# Sheet1.net
KiCad netlist of a schematic drawn in Altium Designer
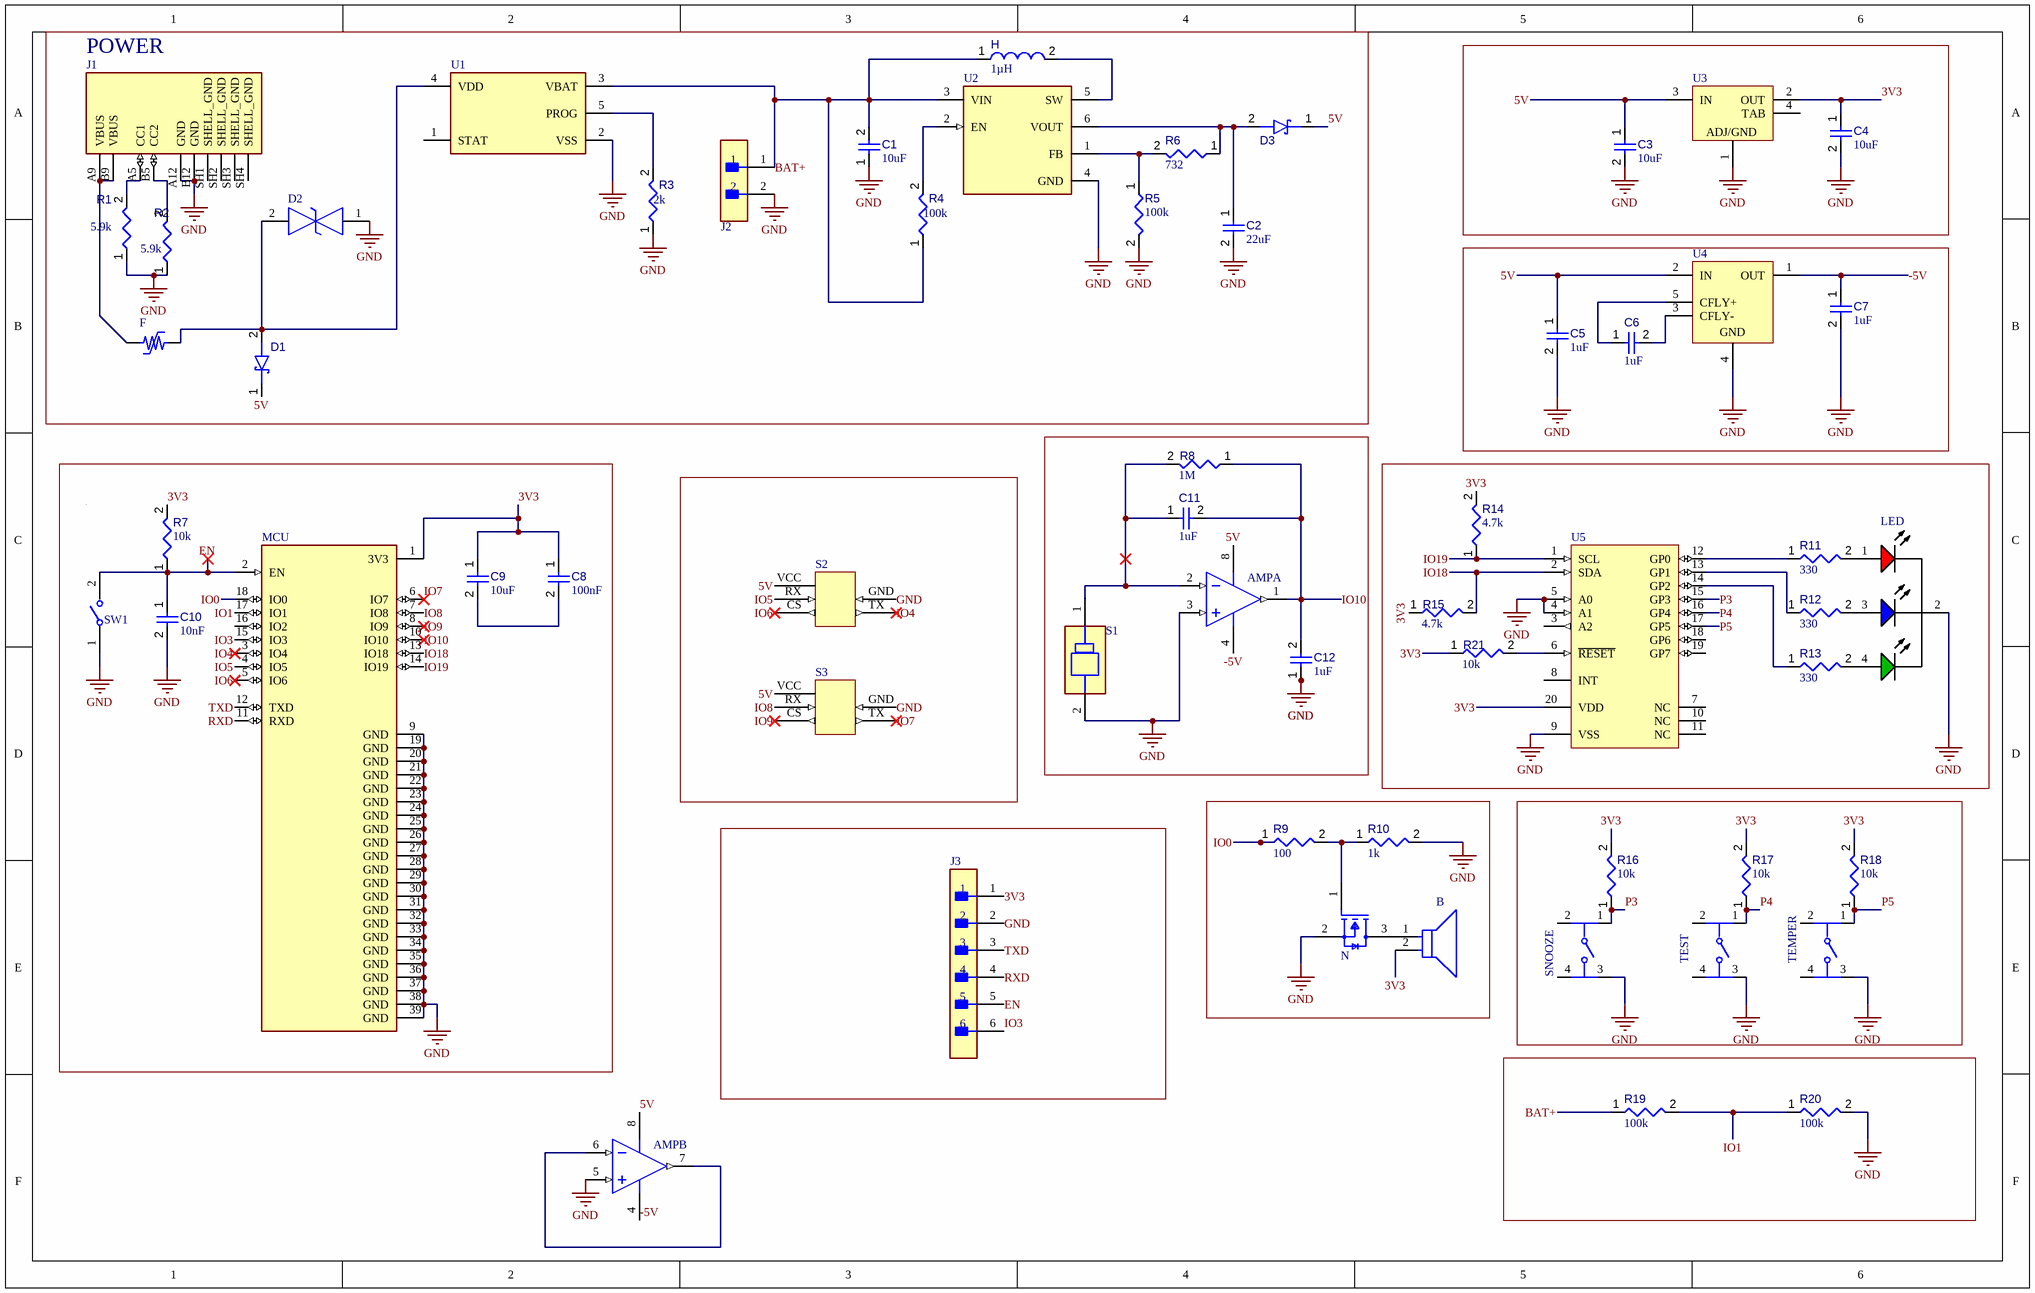
[diagram p0: Sheet1.SchDoc]

(export (version "E")
  (design (tool "Eeschema 10.0.6"))
  (components
    (comp (ref "AMP")
      (value "AD708SQ/883B")
      (footprint "ADI-Q-8")
      (fields (field (name "GENERIC PART NUMBER") "AD708") (field (name "MANUFACTURER") "Analog Devices"))
      (libsource (lib "Altium Content Vault") (part "ADI-AD708-X-8"))
    )
    (comp (ref "B")
      (value "PS1740P02E")
      (footprint "FP-PS1740P02E-MFG")
      (description "AUDIO PIEZO TRANSDUCER 30V TH")
      (libsource (lib "Altium Content Vault") (part "5f581d31613f872430949aa526fd155"))
    )
    (comp (ref "C1")
      (value "10uF")
      (footprint "CAPC0402(1005)33_L")
      (description "Chip Capacitor, 1nF +/-20%, 50V, 0402, Thickness 0.33 mm")
      (fields (field (name "TOLERANCE") "10%") (field (name "Comment") "Capacitor 1nF +/-20% 50V 0402"))
      (libsource (lib "Vivek Kumawat") (part "CAP-NP-2"))
    )
    (comp (ref "C2")
      (value "22uF")
      (footprint "CAPC0402(1005)33_L")
      (description "Chip Capacitor, 1nF +/-20%, 50V, 0402, Thickness 0.33 mm")
      (fields (field (name "TOLERANCE") "10%") (field (name "Comment") "Capacitor 1nF +/-20% 50V 0402"))
      (libsource (lib "Vivek Kumawat") (part "CAP-NP-2"))
    )
    (comp (ref "C3")
      (value "10uF")
      (footprint "CAPC0402(1005)33_L")
      (description "Chip Capacitor, 1nF +/-20%, 50V, 0402, Thickness 0.33 mm")
      (fields (field (name "TOLERANCE") "10%") (field (name "Comment") "Capacitor 1nF +/-20% 50V 0402"))
      (libsource (lib "Vivek Kumawat") (part "CAP-NP-2"))
    )
    (comp (ref "C4")
      (value "10uF")
      (footprint "CAPC0402(1005)33_L")
      (description "Chip Capacitor, 1nF +/-20%, 50V, 0402, Thickness 0.33 mm")
      (fields (field (name "TOLERANCE") "10%") (field (name "Comment") "Capacitor 1nF +/-20% 50V 0402"))
      (libsource (lib "Vivek Kumawat") (part "CAP-NP-2"))
    )
    (comp (ref "C5")
      (value "1uF")
      (footprint "CAPC0402(1005)33_L")
      (description "Chip Capacitor, 1nF +/-20%, 50V, 0402, Thickness 0.33 mm")
      (fields (field (name "TOLERANCE") "10%") (field (name "Comment") "Capacitor 1nF +/-20% 50V 0402"))
      (libsource (lib "Vivek Kumawat") (part "CAP-NP-2"))
    )
    (comp (ref "C6")
      (value "1uF")
      (footprint "CAPC0402(1005)33_L")
      (description "Chip Capacitor, 1nF +/-20%, 50V, 0402, Thickness 0.33 mm")
      (fields (field (name "TOLERANCE") "10%") (field (name "Comment") "Capacitor 1nF +/-20% 50V 0402"))
      (libsource (lib "Vivek Kumawat") (part "CAP-NP-2"))
    )
    (comp (ref "C7")
      (value "1uF")
      (footprint "CAPC0402(1005)33_L")
      (description "Chip Capacitor, 1nF +/-20%, 50V, 0402, Thickness 0.33 mm")
      (fields (field (name "TOLERANCE") "10%") (field (name "Comment") "Capacitor 1nF +/-20% 50V 0402"))
      (libsource (lib "Vivek Kumawat") (part "CAP-NP-2"))
    )
    (comp (ref "C8")
      (value "100nF")
      (footprint "CAPC0402(1005)33_L")
      (description "Chip Capacitor, 1nF +/-20%, 50V, 0402, Thickness 0.33 mm")
      (fields (field (name "TOLERANCE") "10%") (field (name "Comment") "Capacitor 1nF +/-20% 50V 0402"))
      (libsource (lib "Vivek Kumawat") (part "CAP-NP-2"))
    )
    (comp (ref "C9")
      (value "10uF")
      (footprint "CAPC0402(1005)33_L")
      (description "Chip Capacitor, 1nF +/-20%, 50V, 0402, Thickness 0.33 mm")
      (fields (field (name "TOLERANCE") "10%") (field (name "Comment") "Capacitor 1nF +/-20% 50V 0402"))
      (libsource (lib "Vivek Kumawat") (part "CAP-NP-2"))
    )
    (comp (ref "C10")
      (value "10nF")
      (footprint "CAPC0402(1005)33_L")
      (description "Chip Capacitor, 1nF +/-20%, 50V, 0402, Thickness 0.33 mm")
      (fields (field (name "TOLERANCE") "10%") (field (name "Comment") "Capacitor 1nF +/-20% 50V 0402"))
      (libsource (lib "Vivek Kumawat") (part "CAP-NP-2"))
    )
    (comp (ref "C11")
      (value "1uF")
      (footprint "CAPC0402(1005)33_L")
      (description "Chip Capacitor, 1nF +/-20%, 50V, 0402, Thickness 0.33 mm")
      (fields (field (name "TOLERANCE") "10%") (field (name "Comment") "Capacitor 1nF +/-20% 50V 0402"))
      (libsource (lib "Vivek Kumawat") (part "CAP-NP-2"))
    )
    (comp (ref "C12")
      (value "1uF")
      (footprint "CAPC0402(1005)33_L")
      (description "Chip Capacitor, 1nF +/-20%, 50V, 0402, Thickness 0.33 mm")
      (fields (field (name "TOLERANCE") "10%") (field (name "Comment") "Capacitor 1nF +/-20% 50V 0402"))
      (libsource (lib "Vivek Kumawat") (part "CAP-NP-2"))
    )
    (comp (ref "D1")
      (value "RB520CM-30")
      (footprint "ROHM-VMN2-2_V")
      (description "DIODE SCHOTTKY 30V 100MA VMN2M")
      (libsource (lib "Vivek Kumawat") (part "D-SKY-KA2"))
    )
    (comp (ref "D2")
      (value "ESD05V88D-LC")
      (footprint "ESD05V88DLC")
      (description "Bi-directional TVS Diode for ESD Protection")
      (libsource (lib "Vivek Kumawat") (part "ESD05V88D-LC"))
    )
    (comp (ref "D3")
      (value "RB520CM-30")
      (footprint "ROHM-VMN2-2_V")
      (description "DIODE SCHOTTKY 30V 100MA VMN2M")
      (libsource (lib "Vivek Kumawat") (part "D-SKY-KA2"))
    )
    (comp (ref "F")
      (value "MF-MSMF075-2")
      (footprint "BOUR-MF-MSMF050-2_V")
      (description "PTC Resettable Fuse, 13.2 V, 750 mA, -40 to 85 degC, 2-Pin SMD, RoHS, Tape and Reel")
      (fields (field (name "MANUFACTURER") "Bourns"))
      (libsource (lib "Vivek Kumawat") (part "PPTC-2"))
    )
    (comp (ref "H")
      (value "1µH")
      (footprint "TDK-VLCF5028-2_V")
      (fields
        (field (name "TOLERANCE") "30%")
        (field (name "MANUFACTURER") "TDK")
        (field (name "Comment") "VLCF5028T-2R7N1R8-2")
      )
      (libsource (lib "Vivek Kumawat") (part "IND-2"))
    )
    (comp (ref "J1")
      (value "USB4970-00-A_REVA")
      (footprint "GCT_USB4970-00-A_REVA")
      (description "Type C USB Charging Connector")
      (fields (field (name "MF") "Global Connector Technology") (field (name "MP") "USB4970-00-A"))
      (libsource (lib "Vivek Kumawat") (part "USB4970-00-A_REVA"))
    )
    (comp (ref "J2")
      (value "B02P-VL (LF)(SN)")
      (footprint "FP-B02P-VL_LF_SN-MFG")
      (libsource (lib "Altium Content Vault") (part "3bc925449376181038e59eaffc5286c"))
    )
    (comp (ref "J3")
      (value "MTSW-106-22-L-S-409")
      (footprint "FP-MTSW-106-22-L-S-409-MFG")
      (description "Headers & Wire Housings Variable Height PCB HDR Strps, 0.100\" Pitch")
      (libsource (lib "Altium Content Vault") (part "11692be1245668b174829cb8722fdf5"))
    )
    (comp (ref "LED")
      (value "WP154A4SUREQBFZGC")
      (footprint "KING-WP154A4SUREQBFZGC_V")
      (description "Full Color LED Lamp, Dominant Wavelength RGB 630 / 525 / 465 nm, -40 to 85 degC, 4-Pin THD, RoHS")
      (fields (field (name "MANUFACTURER") "Kingbright"))
      (libsource (lib "Altium Content Vault") (part "LED-RGB-AKAA-4"))
    )
    (comp (ref "MCU")
      (value "ESP32-C3-WROOM-02-H4")
      (footprint "MODULE_ESP32-C3-WROOM-02-H4")
      (fields (field (name "MF") "Espressif Systems"))
      (libsource (lib "Vivek Kumawat") (part "ESP32-C3-WROOM-02-H4"))
    )
    (comp (ref "N")
      (value "AO3400A")
      (footprint "FP-SOT23-MFG")
      (description "MOSFET N-CH 30V 5.7A SOT23")
      (libsource (lib "Altium Content Vault") (part "0a9ea7c96deaaede766a5b531c28de0"))
    )
    (comp (ref "R1")
      (value "5.9k")
      (footprint "RESC0402(1005)_L")
      (description "Chip Resistor, 100 kOhms, +/-1 %, 63 mW, -55 to 155 degC, 0402")
      (fields (field (name "TOLERANCE") "1%") (field (name "POWER") "63mW"))
      (libsource (lib "Vivek Kumawat") (part "RES-2"))
    )
    (comp (ref "R2")
      (value "5.9k")
      (footprint "RESC0402(1005)_L")
      (description "Chip Resistor, 100 kOhms, +/-1 %, 63 mW, -55 to 155 degC, 0402")
      (fields (field (name "TOLERANCE") "1%") (field (name "POWER") "63mW"))
      (libsource (lib "Vivek Kumawat") (part "RES-2"))
    )
    (comp (ref "R3")
      (value "2k")
      (footprint "RESC0402(1005)_L")
      (description "Chip Resistor, 100 kOhms, +/-1 %, 63 mW, -55 to 155 degC, 0402")
      (fields (field (name "TOLERANCE") "1%") (field (name "POWER") "63mW"))
      (libsource (lib "Vivek Kumawat") (part "RES-2"))
    )
    (comp (ref "R4")
      (value "100k")
      (footprint "RESC0402(1005)_L")
      (description "Chip Resistor, 100 kOhms, +/-1 %, 63 mW, -55 to 155 degC, 0402")
      (fields (field (name "TOLERANCE") "1%") (field (name "POWER") "63mW"))
      (libsource (lib "Vivek Kumawat") (part "RES-2"))
    )
    (comp (ref "R5")
      (value "100k")
      (footprint "RESC0402(1005)_L")
      (description "Chip Resistor, 100 kOhms, +/-1 %, 63 mW, -55 to 155 degC, 0402")
      (fields (field (name "TOLERANCE") "1%") (field (name "POWER") "63mW"))
      (libsource (lib "Vivek Kumawat") (part "RES-2"))
    )
    (comp (ref "R6")
      (value "732")
      (footprint "RESC0402(1005)_L")
      (description "Chip Resistor, 100 kOhms, +/-1 %, 63 mW, -55 to 155 degC, 0402")
      (fields (field (name "TOLERANCE") "1%") (field (name "POWER") "63mW"))
      (libsource (lib "Vivek Kumawat") (part "RES-2"))
    )
    (comp (ref "R7")
      (value "10k")
      (footprint "RESC0402(1005)_L")
      (description "Chip Resistor, 100 kOhms, +/-1 %, 63 mW, -55 to 155 degC, 0402")
      (fields (field (name "TOLERANCE") "1%") (field (name "POWER") "63mW"))
      (libsource (lib "Vivek Kumawat") (part "RES-2"))
    )
    (comp (ref "R8")
      (value "1M")
      (footprint "RESC0402(1005)_L")
      (description "Chip Resistor, 100 kOhms, +/-1 %, 63 mW, -55 to 155 degC, 0402")
      (fields (field (name "TOLERANCE") "1%") (field (name "POWER") "63mW"))
      (libsource (lib "Vivek Kumawat") (part "RES-2"))
    )
    (comp (ref "R9")
      (value "100")
      (footprint "RESC0402(1005)_L")
      (description "Chip Resistor, 100 kOhms, +/-1 %, 63 mW, -55 to 155 degC, 0402")
      (fields (field (name "TOLERANCE") "1%") (field (name "POWER") "63mW"))
      (libsource (lib "Vivek Kumawat") (part "RES-2"))
    )
    (comp (ref "R10")
      (value "1k")
      (footprint "RESC0402(1005)_L")
      (description "Chip Resistor, 100 kOhms, +/-1 %, 63 mW, -55 to 155 degC, 0402")
      (fields (field (name "TOLERANCE") "1%") (field (name "POWER") "63mW"))
      (libsource (lib "Vivek Kumawat") (part "RES-2"))
    )
    (comp (ref "R11")
      (value "330")
      (footprint "RESC0402(1005)_L")
      (description "Chip Resistor, 100 kOhms, +/-1 %, 63 mW, -55 to 155 degC, 0402")
      (fields (field (name "TOLERANCE") "1%") (field (name "POWER") "63mW"))
      (libsource (lib "Vivek Kumawat") (part "RES-2"))
    )
    (comp (ref "R12")
      (value "330")
      (footprint "RESC0402(1005)_L")
      (description "Chip Resistor, 100 kOhms, +/-1 %, 63 mW, -55 to 155 degC, 0402")
      (fields (field (name "TOLERANCE") "1%") (field (name "POWER") "63mW"))
      (libsource (lib "Vivek Kumawat") (part "RES-2"))
    )
    (comp (ref "R13")
      (value "330")
      (footprint "RESC0402(1005)_L")
      (description "Chip Resistor, 100 kOhms, +/-1 %, 63 mW, -55 to 155 degC, 0402")
      (fields (field (name "TOLERANCE") "1%") (field (name "POWER") "63mW"))
      (libsource (lib "Vivek Kumawat") (part "RES-2"))
    )
    (comp (ref "R14")
      (value "4.7k")
      (footprint "RESC0402(1005)_L")
      (description "Chip Resistor, 100 kOhms, +/-1 %, 63 mW, -55 to 155 degC, 0402")
      (fields (field (name "TOLERANCE") "1%") (field (name "POWER") "63mW"))
      (libsource (lib "Vivek Kumawat") (part "RES-2"))
    )
    (comp (ref "R15")
      (value "4.7k")
      (footprint "RESC0402(1005)_L")
      (description "Chip Resistor, 100 kOhms, +/-1 %, 63 mW, -55 to 155 degC, 0402")
      (fields (field (name "TOLERANCE") "1%") (field (name "POWER") "63mW"))
      (libsource (lib "Vivek Kumawat") (part "RES-2"))
    )
    (comp (ref "R16")
      (value "10k")
      (footprint "RESC0402(1005)_L")
      (description "Chip Resistor, 100 kOhms, +/-1 %, 63 mW, -55 to 155 degC, 0402")
      (fields (field (name "TOLERANCE") "1%") (field (name "POWER") "63mW"))
      (libsource (lib "Vivek Kumawat") (part "RES-2"))
    )
    (comp (ref "R17")
      (value "10k")
      (footprint "RESC0402(1005)_L")
      (description "Chip Resistor, 100 kOhms, +/-1 %, 63 mW, -55 to 155 degC, 0402")
      (fields (field (name "TOLERANCE") "1%") (field (name "POWER") "63mW"))
      (libsource (lib "Vivek Kumawat") (part "RES-2"))
    )
    (comp (ref "R18")
      (value "10k")
      (footprint "RESC0402(1005)_L")
      (description "Chip Resistor, 100 kOhms, +/-1 %, 63 mW, -55 to 155 degC, 0402")
      (fields (field (name "TOLERANCE") "1%") (field (name "POWER") "63mW"))
      (libsource (lib "Vivek Kumawat") (part "RES-2"))
    )
    (comp (ref "R19")
      (value "100k")
      (footprint "RESC0402(1005)_L")
      (description "Chip Resistor, 100 kOhms, +/-1 %, 63 mW, -55 to 155 degC, 0402")
      (fields (field (name "TOLERANCE") "1%") (field (name "POWER") "63mW"))
      (libsource (lib "Vivek Kumawat") (part "RES-2"))
    )
    (comp (ref "R20")
      (value "100k")
      (footprint "RESC0402(1005)_L")
      (description "Chip Resistor, 100 kOhms, +/-1 %, 63 mW, -55 to 155 degC, 0402")
      (fields (field (name "TOLERANCE") "1%") (field (name "POWER") "63mW"))
      (libsource (lib "Vivek Kumawat") (part "RES-2"))
    )
    (comp (ref "R21")
      (value "10k")
      (footprint "RESC0402(1005)_L")
      (description "Chip Resistor, 100 kOhms, +/-1 %, 63 mW, -55 to 155 degC, 0402")
      (fields (field (name "TOLERANCE") "1%") (field (name "POWER") "63mW"))
      (libsource (lib "Vivek Kumawat") (part "RES-2"))
    )
    (comp (ref "S1")
      (value "TGS5141-P00")
      (footprint "FP-TGS5141-P00-MFG")
      (description "SENSOR CARBON MONOXIDE")
      (fields
        (field (name "OCTOPART") "https://octopart.com/tgs5141-p00-figaro-103046867")
        (field (name "MANUFACTURER") "Figaro")
      )
      (libsource (lib "Altium Content Vault") (part "f3ccaba9b869ac16705ba1b5e0c8c7d"))
    )
    (comp (ref "S2")
      (value "C1N_2654_40D-Symbol-1")
      (footprint "C1N_2654_40D.PcbLib")
      (libsource (lib "Vivek Kumawat") (part "C1N_2654_40D-Symbol-1"))
    )
    (comp (ref "S3")
      (value "C1N_2654_40D-Symbol-1")
      (footprint "C1N_2654_40D.PcbLib")
      (libsource (lib "Vivek Kumawat") (part "C1N_2654_40D-Symbol-1"))
    )
    (comp (ref "SNOOZE")
      (value "B3F-1006")
      (footprint "FP-B3F-1006-MFG")
      (description "SWITCH TACTILE SPST-NO 0.05A 24V")
      (libsource (lib "Altium Content Vault") (part "b8895f3f4cefb76e1819d2863dba89b"))
    )
    (comp (ref "SW1")
      (value "B3U-1000P")
      (footprint "FP-B3U-1000P-MFG")
      (description "SWITCH TACTILE SPST-NO 0.05A 12V")
      (libsource (lib "Altium Content Vault") (part "ae622034201233ca1abcedc05908f33"))
    )
    (comp (ref "TEMPER")
      (value "B3F-1006")
      (footprint "FP-B3F-1006-MFG")
      (description "SWITCH TACTILE SPST-NO 0.05A 24V")
      (libsource (lib "Altium Content Vault") (part "b8895f3f4cefb76e1819d2863dba89b"))
    )
    (comp (ref "TEST")
      (value "B3F-1006")
      (footprint "FP-B3F-1006-MFG")
      (description "SWITCH TACTILE SPST-NO 0.05A 24V")
      (libsource (lib "Altium Content Vault") (part "b8895f3f4cefb76e1819d2863dba89b"))
    )
    (comp (ref "U1")
      (value "MCP73831T-2ACI/OT")
      (footprint "FP-C04-091-OT-IPC_B")
      (description "IC CONTROLLR LI-ION 4.2V SOT23-5")
      (libsource (lib "Altium Content Vault") (part "61f5a3bb3429d9e0caadea342aa3b19"))
    )
    (comp (ref "U2")
      (value "TPS61023DRLR")
      (footprint "FP-DRL0006A-MFG")
      (description "FINISH GOODS FOR TPS61023")
      (libsource (lib "Altium Content Vault") (part "b28b3e956a4ad07201ce69f9d09f9a8"))
    )
    (comp (ref "U3")
      (value "NCP1117ST33T3G")
      (footprint "ONSC-SOT-223-4-318H-01_A_V")
      (fields (field (name "MANUFACTURER") "ON Semiconductor"))
      (libsource (lib "Vivek Kumawat") (part "ONSC-NCP1117-SOT223-4"))
    )
    (comp (ref "U4")
      (value "TPS60403DBVRG4")
      (footprint "TI-DBV5_M")
      (fields (field (name "MANUFACTURER") "Texas Instruments"))
      (libsource (lib "Altium Content Vault") (part "TI-TPS6040X-DBV5"))
    )
    (comp (ref "U5")
      (value "MCP23008-E/SS")
      (footprint "SSOP-SS20_N")
      (description "8-Bit I/O Expander with Serial Interface, 20-Pin SSOP, Extended Temperature")
      (libsource (lib "Altium Content Vault") (part "PR-BUSIC-MCP23008-20"))
    )
  )
  (nets
    (net (code "1") (name "/-5V") (class "Default")
      (node (ref "AMP") (pin "4") (pinfunction "-VS_4") (pintype "power_in"))
      (node (ref "C7") (pin "1") (pinfunction "1_1") (pintype "passive"))
      (node (ref "U4") (pin "1") (pinfunction "OUT_1") (pintype "power_in"))
    )
    (net (code "2") (name "/3V3") (class "Default")
      (node (ref "B") (pin "2") (pinfunction "2_2") (pintype "passive"))
      (node (ref "C4") (pin "1") (pinfunction "1_1") (pintype "passive"))
      (node (ref "C8") (pin "1") (pinfunction "1_1") (pintype "passive"))
      (node (ref "C9") (pin "1") (pinfunction "1_1") (pintype "passive"))
      (node (ref "J3") (pin "1") (pinfunction "1_1") (pintype "passive"))
      (node (ref "MCU") (pin "1") (pinfunction "3V3_1") (pintype "power_in"))
      (node (ref "R14") (pin "2") (pinfunction "2_2") (pintype "passive"))
      (node (ref "R15") (pin "1") (pinfunction "1_1") (pintype "passive"))
      (node (ref "R16") (pin "2") (pinfunction "2_2") (pintype "passive"))
      (node (ref "R17") (pin "2") (pinfunction "2_2") (pintype "passive"))
      (node (ref "R18") (pin "2") (pinfunction "2_2") (pintype "passive"))
      (node (ref "R21") (pin "1") (pinfunction "1_1") (pintype "passive"))
      (node (ref "R7") (pin "2") (pinfunction "2_2") (pintype "passive"))
      (node (ref "U3") (pin "2") (pinfunction "OUT_2") (pintype "power_in"))
      (node (ref "U5") (pin "20") (pinfunction "VDD_20") (pintype "power_in"))
    )
    (net (code "3") (name "/5V") (class "Default")
      (node (ref "AMP") (pin "8") (pinfunction "+VS_8") (pintype "power_in"))
      (node (ref "C3") (pin "1") (pinfunction "1_1") (pintype "passive"))
      (node (ref "C5") (pin "1") (pinfunction "1_1") (pintype "passive"))
      (node (ref "D1") (pin "1") (pinfunction "K_1") (pintype "passive"))
      (node (ref "D3") (pin "1") (pinfunction "K_1") (pintype "passive"))
      (node (ref "S2") (pin "VCC") (pintype "power_in"))
      (node (ref "S3") (pin "VCC") (pintype "power_in"))
      (node (ref "U3") (pin "3") (pinfunction "IN_3") (pintype "power_in"))
      (node (ref "U4") (pin "2") (pinfunction "IN_2") (pintype "power_in"))
    )
    (net (code "4") (name "/BAT+") (class "Default")
      (node (ref "C1") (pin "2") (pinfunction "2_2") (pintype "passive"))
      (node (ref "H") (pin "1") (pinfunction "1_1") (pintype "passive"))
      (node (ref "J2") (pin "1") (pinfunction "1_1") (pintype "passive"))
      (node (ref "R19") (pin "1") (pinfunction "1_1") (pintype "passive"))
      (node (ref "R4") (pin "1") (pinfunction "1_1") (pintype "passive"))
      (node (ref "U1") (pin "3") (pinfunction "VBAT_3") (pintype "power_in"))
      (node (ref "U2") (pin "3") (pinfunction "VIN_3") (pintype "power_in"))
    )
    (net (code "5") (name "/EN") (class "Default")
      (node (ref "C10") (pin "1") (pinfunction "1_1") (pintype "passive"))
      (node (ref "J3") (pin "5") (pinfunction "5_5") (pintype "passive"))
      (node (ref "MCU") (pin "2") (pinfunction "EN_2") (pintype "input"))
      (node (ref "R7") (pin "1") (pinfunction "1_1") (pintype "passive"))
      (node (ref "SW1") (pin "2") (pinfunction "2_2") (pintype "passive"))
    )
    (net (code "6") (name "/IO0") (class "Default")
      (node (ref "MCU") (pin "18") (pinfunction "IO0_18") (pintype "bidirectional"))
      (node (ref "R9") (pin "1") (pinfunction "1_1") (pintype "passive"))
    )
    (net (code "7") (name "/IO1") (class "Default")
      (node (ref "MCU") (pin "17") (pinfunction "IO1_17") (pintype "bidirectional"))
      (node (ref "R19") (pin "2") (pinfunction "2_2") (pintype "passive"))
      (node (ref "R20") (pin "1") (pinfunction "1_1") (pintype "passive"))
    )
    (net (code "8") (name "/IO3") (class "Default")
      (node (ref "J3") (pin "6") (pinfunction "6_6") (pintype "passive"))
      (node (ref "MCU") (pin "15") (pinfunction "IO3_15") (pintype "bidirectional"))
    )
    (net (code "9") (name "/IO4") (class "Default")
      (node (ref "MCU") (pin "3") (pinfunction "IO4_3") (pintype "bidirectional"))
      (node (ref "S2") (pin "TX") (pintype "output"))
    )
    (net (code "10") (name "/IO5") (class "Default")
      (node (ref "MCU") (pin "4") (pinfunction "IO5_4") (pintype "bidirectional"))
      (node (ref "S2") (pin "RX") (pintype "input"))
    )
    (net (code "11") (name "/IO6") (class "Default")
      (node (ref "MCU") (pin "5") (pinfunction "IO6_5") (pintype "bidirectional"))
      (node (ref "S2") (pin "CS") (pintype "output"))
    )
    (net (code "12") (name "/IO7") (class "Default")
      (node (ref "MCU") (pin "6") (pinfunction "IO7_6") (pintype "bidirectional"))
      (node (ref "S3") (pin "TX") (pintype "output"))
    )
    (net (code "13") (name "/IO8") (class "Default")
      (node (ref "MCU") (pin "7") (pinfunction "IO8_7") (pintype "bidirectional"))
      (node (ref "S3") (pin "RX") (pintype "input"))
    )
    (net (code "14") (name "/IO9") (class "Default")
      (node (ref "MCU") (pin "8") (pinfunction "IO9_8") (pintype "bidirectional"))
      (node (ref "S3") (pin "CS") (pintype "output"))
    )
    (net (code "15") (name "/IO10") (class "Default")
      (node (ref "AMP") (pin "1") (pinfunction "OUT_A_1") (pintype "output"))
      (node (ref "C11") (pin "2") (pinfunction "2_2") (pintype "passive"))
      (node (ref "C12") (pin "2") (pinfunction "2_2") (pintype "passive"))
      (node (ref "MCU") (pin "10") (pinfunction "IO10_10") (pintype "bidirectional"))
      (node (ref "R8") (pin "1") (pinfunction "1_1") (pintype "passive"))
    )
    (net (code "16") (name "/IO18") (class "Default")
      (node (ref "MCU") (pin "13") (pinfunction "IO18_13") (pintype "bidirectional"))
      (node (ref "R15") (pin "2") (pinfunction "2_2") (pintype "passive"))
      (node (ref "U5") (pin "2") (pinfunction "SDA_2") (pintype "input"))
    )
    (net (code "17") (name "/IO19") (class "Default")
      (node (ref "MCU") (pin "14") (pinfunction "IO19_14") (pintype "bidirectional"))
      (node (ref "R14") (pin "1") (pinfunction "1_1") (pintype "passive"))
      (node (ref "U5") (pin "1") (pinfunction "SCL_1") (pintype "input"))
    )
    (net (code "18") (name "/P3") (class "Default")
      (node (ref "R16") (pin "1") (pinfunction "1_1") (pintype "passive"))
      (node (ref "SNOOZE") (pin "1") (pinfunction "1_1") (pintype "passive"))
      (node (ref "U5") (pin "15") (pinfunction "GP3_15") (pintype "bidirectional"))
    )
    (net (code "19") (name "/P4") (class "Default")
      (node (ref "R17") (pin "1") (pinfunction "1_1") (pintype "passive"))
      (node (ref "TEST") (pin "1") (pinfunction "1_1") (pintype "passive"))
      (node (ref "U5") (pin "16") (pinfunction "GP4_16") (pintype "bidirectional"))
    )
    (net (code "20") (name "/P5") (class "Default")
      (node (ref "R18") (pin "1") (pinfunction "1_1") (pintype "passive"))
      (node (ref "TEMPER") (pin "1") (pinfunction "1_1") (pintype "passive"))
      (node (ref "U5") (pin "17") (pinfunction "GP5_17") (pintype "bidirectional"))
    )
    (net (code "21") (name "/RXD") (class "Default")
      (node (ref "J3") (pin "4") (pinfunction "4_4") (pintype "passive"))
      (node (ref "MCU") (pin "11") (pinfunction "RXD_11") (pintype "bidirectional"))
    )
    (net (code "22") (name "/TXD") (class "Default")
      (node (ref "J3") (pin "3") (pinfunction "3_3") (pintype "passive"))
      (node (ref "MCU") (pin "12") (pinfunction "TXD_12") (pintype "bidirectional"))
    )
    (net (code "23") (name "GND") (class "Default")
      (node (ref "AMP") (pin "3") (pinfunction "+IN_A_3") (pintype "input"))
      (node (ref "AMP") (pin "5") (pinfunction "+IN_B_5") (pintype "input"))
      (node (ref "C1") (pin "1") (pinfunction "1_1") (pintype "passive"))
      (node (ref "C10") (pin "2") (pinfunction "2_2") (pintype "passive"))
      (node (ref "C12") (pin "1") (pinfunction "1_1") (pintype "passive"))
      (node (ref "C2") (pin "2") (pinfunction "2_2") (pintype "passive"))
      (node (ref "C3") (pin "2") (pinfunction "2_2") (pintype "passive"))
      (node (ref "C4") (pin "2") (pinfunction "2_2") (pintype "passive"))
      (node (ref "C5") (pin "2") (pinfunction "2_2") (pintype "passive"))
      (node (ref "C7") (pin "2") (pinfunction "2_2") (pintype "passive"))
      (node (ref "D2") (pin "1") (pinfunction "1_1") (pintype "passive"))
      (node (ref "J1") (pin "A12") (pinfunction "GND_A12") (pintype "power_in"))
      (node (ref "J1") (pin "B12") (pinfunction "GND_B12") (pintype "power_in"))
      (node (ref "J2") (pin "2") (pinfunction "2_2") (pintype "passive"))
      (node (ref "J3") (pin "2") (pinfunction "2_2") (pintype "passive"))
      (node (ref "LED") (pin "2") (pinfunction "CATHODE_2") (pintype "passive"))
      (node (ref "MCU") (pin "19") (pinfunction "GND_19") (pintype "power_in"))
      (node (ref "MCU") (pin "20") (pinfunction "GND_20") (pintype "power_in"))
      (node (ref "MCU") (pin "21") (pinfunction "GND_21") (pintype "power_in"))
      (node (ref "MCU") (pin "22") (pinfunction "GND_22") (pintype "power_in"))
      (node (ref "MCU") (pin "23") (pinfunction "GND_23") (pintype "power_in"))
      (node (ref "MCU") (pin "24") (pinfunction "GND_24") (pintype "power_in"))
      (node (ref "MCU") (pin "25") (pinfunction "GND_25") (pintype "power_in"))
      (node (ref "MCU") (pin "26") (pinfunction "GND_26") (pintype "power_in"))
      (node (ref "MCU") (pin "27") (pinfunction "GND_27") (pintype "power_in"))
      (node (ref "MCU") (pin "28") (pinfunction "GND_28") (pintype "power_in"))
      (node (ref "MCU") (pin "29") (pinfunction "GND_29") (pintype "power_in"))
      (node (ref "MCU") (pin "30") (pinfunction "GND_30") (pintype "power_in"))
      (node (ref "MCU") (pin "31") (pinfunction "GND_31") (pintype "power_in"))
      (node (ref "MCU") (pin "32") (pinfunction "GND_32") (pintype "power_in"))
      (node (ref "MCU") (pin "33") (pinfunction "GND_33") (pintype "power_in"))
      (node (ref "MCU") (pin "34") (pinfunction "GND_34") (pintype "power_in"))
      (node (ref "MCU") (pin "35") (pinfunction "GND_35") (pintype "power_in"))
      (node (ref "MCU") (pin "36") (pinfunction "GND_36") (pintype "power_in"))
      (node (ref "MCU") (pin "37") (pinfunction "GND_37") (pintype "power_in"))
      (node (ref "MCU") (pin "38") (pinfunction "GND_38") (pintype "power_in"))
      (node (ref "MCU") (pin "39") (pinfunction "GND_39") (pintype "power_in"))
      (node (ref "MCU") (pin "9") (pinfunction "GND_9") (pintype "power_in"))
      (node (ref "N") (pin "2") (pinfunction "S_2") (pintype "passive"))
      (node (ref "R1") (pin "1") (pinfunction "1_1") (pintype "passive"))
      (node (ref "R10") (pin "2") (pinfunction "2_2") (pintype "passive"))
      (node (ref "R2") (pin "1") (pinfunction "1_1") (pintype "passive"))
      (node (ref "R20") (pin "2") (pinfunction "2_2") (pintype "passive"))
      (node (ref "R3") (pin "1") (pinfunction "1_1") (pintype "passive"))
      (node (ref "R5") (pin "2") (pinfunction "2_2") (pintype "passive"))
      (node (ref "S1") (pin "2") (pinfunction "Counter_2") (pintype "passive"))
      (node (ref "S2") (pin "GND") (pintype "input"))
      (node (ref "S3") (pin "GND") (pintype "input"))
      (node (ref "SNOOZE") (pin "3") (pinfunction "3_3") (pintype "passive"))
      (node (ref "SW1") (pin "1") (pinfunction "1_1") (pintype "passive"))
      (node (ref "TEMPER") (pin "3") (pinfunction "3_3") (pintype "passive"))
      (node (ref "TEST") (pin "3") (pinfunction "3_3") (pintype "passive"))
      (node (ref "U1") (pin "2") (pinfunction "VSS_2") (pintype "power_in"))
      (node (ref "U2") (pin "4") (pinfunction "GND_4") (pintype "power_in"))
      (node (ref "U3") (pin "1") (pinfunction "ADJ/GND_1") (pintype "passive"))
      (node (ref "U4") (pin "4") (pinfunction "GND_4") (pintype "power_in"))
      (node (ref "U5") (pin "4") (pinfunction "A1_4") (pintype "input"))
      (node (ref "U5") (pin "5") (pinfunction "A0_5") (pintype "input"))
      (node (ref "U5") (pin "9") (pinfunction "VSS_9") (pintype "power_in"))
    )
    (net (code "24") (name "Net-(AMPA--IN_A)") (class "Default")
      (node (ref "AMP") (pin "2") (pinfunction "-IN_A_2") (pintype "input"))
      (node (ref "C11") (pin "1") (pinfunction "1_1") (pintype "passive"))
      (node (ref "R8") (pin "2") (pinfunction "2_2") (pintype "passive"))
      (node (ref "S1") (pin "1") (pinfunction "Working_1") (pintype "passive"))
    )
    (net (code "25") (name "Net-(AMPB--IN_B)") (class "Default")
      (node (ref "AMP") (pin "6") (pinfunction "-IN_B_6") (pintype "input"))
      (node (ref "AMP") (pin "7") (pinfunction "OUT_B_7") (pintype "output"))
    )
    (net (code "26") (name "Net-(C8-Pad2)") (class "Default")
      (node (ref "C8") (pin "2") (pinfunction "2_2") (pintype "passive"))
      (node (ref "C9") (pin "2") (pinfunction "2_2") (pintype "passive"))
    )
    (net (code "27") (name "Net-(D1-A)") (class "Default")
      (node (ref "D1") (pin "2") (pinfunction "A_2") (pintype "passive"))
      (node (ref "D2") (pin "2") (pinfunction "2_2") (pintype "passive"))
      (node (ref "F") (pin "2") (pinfunction "2_2") (pintype "passive"))
      (node (ref "U1") (pin "4") (pinfunction "VDD_4") (pintype "power_in"))
    )
    (net (code "28") (name "Net-(D3-A)") (class "Default")
      (node (ref "C2") (pin "1") (pinfunction "1_1") (pintype "passive"))
      (node (ref "D3") (pin "2") (pinfunction "A_2") (pintype "passive"))
      (node (ref "R6") (pin "1") (pinfunction "1_1") (pintype "passive"))
      (node (ref "U2") (pin "6") (pinfunction "VOUT_6") (pintype "power_in"))
    )
    (net (code "29") (name "Net-(F-Pad1)") (class "Default")
      (node (ref "F") (pin "1") (pinfunction "1_1") (pintype "passive"))
      (node (ref "J1") (pin "A9") (pinfunction "VBUS_A9") (pintype "power_in"))
      (node (ref "J1") (pin "B9") (pinfunction "VBUS_B9") (pintype "power_in"))
    )
    (net (code "30") (name "Net-(J1-CC1)") (class "Default")
      (node (ref "J1") (pin "A5") (pinfunction "CC1_A5") (pintype "bidirectional"))
      (node (ref "R1") (pin "2") (pinfunction "2_2") (pintype "passive"))
    )
    (net (code "31") (name "Net-(J1-CC2)") (class "Default")
      (node (ref "J1") (pin "B5") (pinfunction "CC2_B5") (pintype "bidirectional"))
      (node (ref "R2") (pin "2") (pinfunction "2_2") (pintype "passive"))
    )
    (net (code "32") (name "Net-(LED-BLUE)") (class "Default")
      (node (ref "LED") (pin "3") (pinfunction "BLUE_3") (pintype "passive"))
      (node (ref "R12") (pin "2") (pinfunction "2_2") (pintype "passive"))
    )
    (net (code "33") (name "Net-(LED-GREEN)") (class "Default")
      (node (ref "LED") (pin "4") (pinfunction "GREEN_4") (pintype "passive"))
      (node (ref "R13") (pin "2") (pinfunction "2_2") (pintype "passive"))
    )
    (net (code "34") (name "Net-(LED-RED)") (class "Default")
      (node (ref "LED") (pin "1") (pinfunction "RED_1") (pintype "passive"))
      (node (ref "R11") (pin "2") (pinfunction "2_2") (pintype "passive"))
    )
    (net (code "35") (name "Net-(N-D)") (class "Default")
      (node (ref "B") (pin "1") (pinfunction "1_1") (pintype "passive"))
      (node (ref "N") (pin "3") (pinfunction "D_3") (pintype "passive"))
    )
    (net (code "36") (name "Net-(N-G)") (class "Default")
      (node (ref "N") (pin "1") (pinfunction "G_1") (pintype "passive"))
      (node (ref "R10") (pin "1") (pinfunction "1_1") (pintype "passive"))
      (node (ref "R9") (pin "2") (pinfunction "2_2") (pintype "passive"))
    )
    (net (code "37") (name "Net-(U1-PROG)") (class "Default")
      (node (ref "R3") (pin "2") (pinfunction "2_2") (pintype "passive"))
      (node (ref "U1") (pin "5") (pinfunction "PROG_5") (pintype "passive"))
    )
    (net (code "38") (name "Net-(U2-EN)") (class "Default")
      (node (ref "R4") (pin "2") (pinfunction "2_2") (pintype "passive"))
      (node (ref "U2") (pin "2") (pinfunction "EN_2") (pintype "input"))
    )
    (net (code "39") (name "Net-(U2-FB)") (class "Default")
      (node (ref "R5") (pin "1") (pinfunction "1_1") (pintype "passive"))
      (node (ref "R6") (pin "2") (pinfunction "2_2") (pintype "passive"))
      (node (ref "U2") (pin "1") (pinfunction "FB_1") (pintype "passive"))
    )
    (net (code "40") (name "Net-(U2-SW)") (class "Default")
      (node (ref "H") (pin "2") (pinfunction "2_2") (pintype "passive"))
      (node (ref "U2") (pin "5") (pinfunction "SW_5") (pintype "passive"))
    )
    (net (code "41") (name "Net-(U4-CFLY+)") (class "Default")
      (node (ref "C6") (pin "1") (pinfunction "1_1") (pintype "passive"))
      (node (ref "U4") (pin "5") (pinfunction "CFLY+_5") (pintype "passive"))
    )
    (net (code "42") (name "Net-(U4-CFLY-)") (class "Default")
      (node (ref "C6") (pin "2") (pinfunction "2_2") (pintype "passive"))
      (node (ref "U4") (pin "3") (pinfunction "CFLY-_3") (pintype "passive"))
    )
    (net (code "43") (name "Net-(U5-GP0)") (class "Default")
      (node (ref "R11") (pin "1") (pinfunction "1_1") (pintype "passive"))
      (node (ref "U5") (pin "12") (pinfunction "GP0_12") (pintype "bidirectional"))
    )
    (net (code "44") (name "Net-(U5-GP1)") (class "Default")
      (node (ref "R12") (pin "1") (pinfunction "1_1") (pintype "passive"))
      (node (ref "U5") (pin "13") (pinfunction "GP1_13") (pintype "bidirectional"))
    )
    (net (code "45") (name "Net-(U5-GP2)") (class "Default")
      (node (ref "R13") (pin "1") (pinfunction "1_1") (pintype "passive"))
      (node (ref "U5") (pin "14") (pinfunction "GP2_14") (pintype "bidirectional"))
    )
    (net (code "46") (name "Net-(U5-~{RESET})") (class "Default")
      (node (ref "R21") (pin "2") (pinfunction "2_2") (pintype "passive"))
      (node (ref "U5") (pin "6") (pinfunction "~{RESET}_6") (pintype "input"))
    )
    (net (code "47") (name "unconnected-(J1-SHELL_GND-PadSH1)") (class "Default")
      (node (ref "J1") (pin "SH1") (pinfunction "SHELL_GND_SH1") (pintype "power_in"))
    )
    (net (code "48") (name "unconnected-(J1-SHELL_GND-PadSH2)") (class "Default")
      (node (ref "J1") (pin "SH2") (pinfunction "SHELL_GND_SH2") (pintype "power_in"))
    )
    (net (code "49") (name "unconnected-(J1-SHELL_GND-PadSH3)") (class "Default")
      (node (ref "J1") (pin "SH3") (pinfunction "SHELL_GND_SH3") (pintype "power_in"))
    )
    (net (code "50") (name "unconnected-(J1-SHELL_GND-PadSH4)") (class "Default")
      (node (ref "J1") (pin "SH4") (pinfunction "SHELL_GND_SH4") (pintype "power_in"))
    )
    (net (code "51") (name "unconnected-(MCU-IO2-Pad16)") (class "Default")
      (node (ref "MCU") (pin "16") (pinfunction "IO2_16") (pintype "bidirectional"))
    )
    (net (code "52") (name "unconnected-(SNOOZE-Pad2)") (class "Default")
      (node (ref "SNOOZE") (pin "2") (pinfunction "2_2") (pintype "passive"))
    )
    (net (code "53") (name "unconnected-(SNOOZE-Pad4)") (class "Default")
      (node (ref "SNOOZE") (pin "4") (pinfunction "4_4") (pintype "passive"))
    )
    (net (code "54") (name "unconnected-(TEMPER-Pad2)") (class "Default")
      (node (ref "TEMPER") (pin "2") (pinfunction "2_2") (pintype "passive"))
    )
    (net (code "55") (name "unconnected-(TEMPER-Pad4)") (class "Default")
      (node (ref "TEMPER") (pin "4") (pinfunction "4_4") (pintype "passive"))
    )
    (net (code "56") (name "unconnected-(TEST-Pad2)") (class "Default")
      (node (ref "TEST") (pin "2") (pinfunction "2_2") (pintype "passive"))
    )
    (net (code "57") (name "unconnected-(TEST-Pad4)") (class "Default")
      (node (ref "TEST") (pin "4") (pinfunction "4_4") (pintype "passive"))
    )
    (net (code "58") (name "unconnected-(U1-STAT-Pad1)") (class "Default")
      (node (ref "U1") (pin "1") (pinfunction "STAT_1") (pintype "passive"))
    )
    (net (code "59") (name "unconnected-(U3-TAB-Pad4)") (class "Default")
      (node (ref "U3") (pin "4") (pinfunction "TAB_4") (pintype "passive"))
    )
    (net (code "60") (name "unconnected-(U5-A2-Pad3)") (class "Default")
      (node (ref "U5") (pin "3") (pinfunction "A2_3") (pintype "output"))
    )
    (net (code "61") (name "unconnected-(U5-GP6-Pad18)") (class "Default")
      (node (ref "U5") (pin "18") (pinfunction "GP6_18") (pintype "bidirectional"))
    )
    (net (code "62") (name "unconnected-(U5-GP7-Pad19)") (class "Default")
      (node (ref "U5") (pin "19") (pinfunction "GP7_19") (pintype "bidirectional"))
    )
    (net (code "63") (name "unconnected-(U5-INT-Pad8)") (class "Default")
      (node (ref "U5") (pin "8") (pinfunction "INT_8") (pintype "open_collector"))
    )
    (net (code "64") (name "unconnected-(U5-NC-Pad7)") (class "Default")
      (node (ref "U5") (pin "7") (pinfunction "NC_7") (pintype "passive"))
    )
    (net (code "65") (name "unconnected-(U5-NC-Pad10)") (class "Default")
      (node (ref "U5") (pin "10") (pinfunction "NC_10") (pintype "passive"))
    )
    (net (code "66") (name "unconnected-(U5-NC-Pad11)") (class "Default")
      (node (ref "U5") (pin "11") (pinfunction "NC_11") (pintype "passive"))
    )
  )
)
